# PMIC.net
KiCad netlist of a schematic drawn in Altium Designer
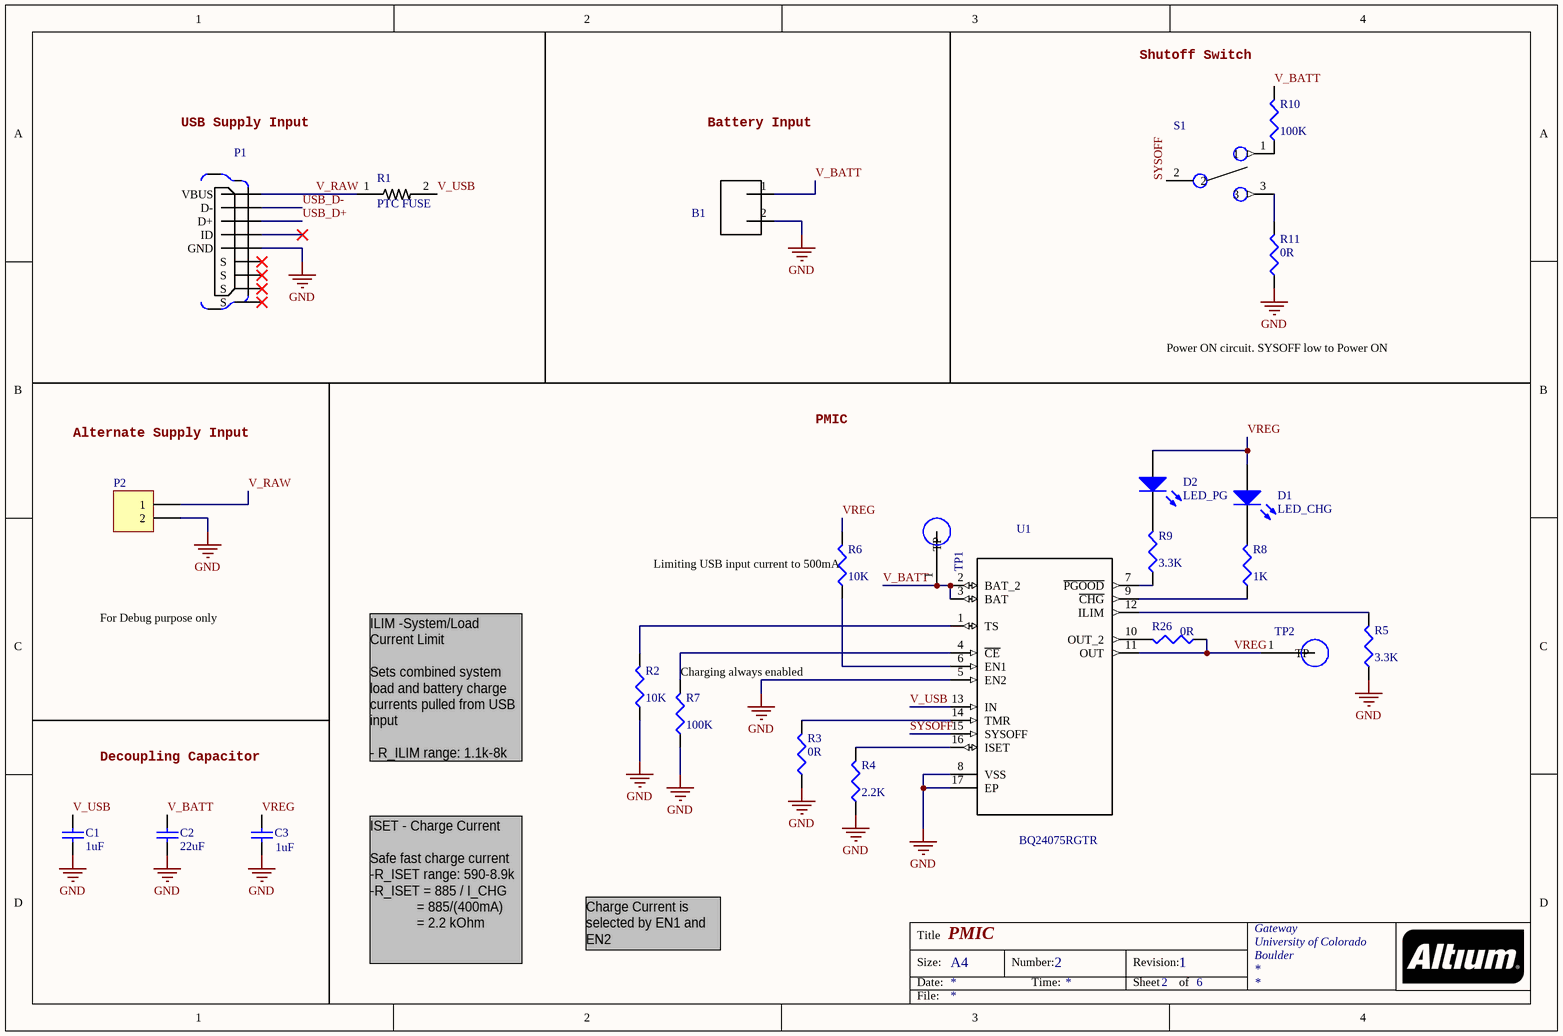
[diagram p0: PMIC.SchDoc]

(export (version "E")
  (design (tool "Eeschema 10.0.6"))
  (components
    (comp (ref "B1")
      (value "VBATT")
      (footprint "S2B-PH-SM4-TB(LF)(SN)")
      (description "CONN HEADER PH SIDE 2POS 2MM SMD")
      (fields
        (field (name "DIGI-KEY PART NUMBER") "455-1749-1-ND")
        (field (name "MANUFACTURER") "JST Sales America Inc.")
      )
      (libsource (lib "S2B-PH-SM4-TB_LF__SN_") (part "S2B-PH-SM4-TB(LF)(SN)"))
    )
    (comp (ref "C1")
      (value "1uF")
      (footprint "1608[0603]")
      (description "CAP CER 1UF 10V X7R 0603")
      (fields
        (field (name "DIGI-KEY PART NUMBER") "1276-1946-1-ND")
        (field (name "MANUFACTURER") "Samsung Electro-Mechanics")
      )
      (libsource (lib "Miscellaneous Devices") (part "Cap Semi"))
    )
    (comp (ref "C2")
      (value "22uF")
      (footprint "1608[0603]")
      (description "CAP CER 22UF 10V X5R 0603")
      (fields
        (field (name "MANUFACTURER") "Samsung Electro-Mechanics")
        (field (name "MANUFACTURER PART NUMBER") "CL10A226MPCNUBE")
        (field (name "PUBLISHER") "Altium Limited")
      )
      (libsource (lib "Miscellaneous Devices") (part "Cap"))
    )
    (comp (ref "C3")
      (value "1uF")
      (footprint "1608[0603]")
      (description "CAP CER 1UF 10V X7R 0603")
      (fields
        (field (name "DIGI-KEY PART NUMBER") "1276-1946-1-ND")
        (field (name "MANUFACTURER") "Samsung Electro-Mechanics")
      )
      (libsource (lib "Miscellaneous Devices") (part "Cap Semi"))
    )
    (comp (ref "D1")
      (value "LED_CHG")
      (footprint "1608[0603]")
      (description "Blue 470nm LED Indication - Discrete 2.85V 0603 (1608 Metric)")
      (fields
        (field (name "DIGI-KEY PART NUMBER") "475-2816-1-ND")
        (field (name "MANUFACTURER") "OSRAM Opto Semiconductors Inc.")
      )
      (libsource (lib "Miscellaneous Devices") (part "LED2"))
    )
    (comp (ref "D2")
      (value "LED_PG")
      (footprint "1608[0603]")
      (description "LED GREEN DIFFUSED 0603 SMD")
      (fields
        (field (name "DIGI-KEY PART NUMBER") "475-3118-1-ND")
        (field (name "MANUFACTURER") "OSRAM Opto Semiconductors Inc.")
      )
      (libsource (lib "Miscellaneous Devices") (part "LED2"))
    )
    (comp (ref "P1")
      (value "10104111-0001LF")
      (footprint "FRAMATOME_10104111-0001LF")
      (description "Micro Usb, 2.0 Type Ab, Receptacle, Th")
      (fields
        (field (name "DIGI-KEY PART NUMBER") "609-4053-1-ND")
        (field (name "MANUFACTURER") "Amphenol FCI")
      )
      (libsource (lib "USB-connector") (part "10104111-0001LF"))
    )
    (comp (ref "P2")
      (value "~")
      (footprint "HDR1X2")
      (description "Header, 2-Pin")
      (libsource (lib "Miscellaneous Connectors") (part "Header 2"))
    )
    (comp (ref "R1")
      (value "PTC FUSE")
      (footprint "RESC3216X125N")
      (description "PTC RESET FUSE 6V 500MA 1206")
      (fields (field (name "MANUFACTURER") "Bel Fuse") (field (name "MP") "0ZCA0075FF2G"))
      (libsource (lib "PTC-1206") (part "0ZCA0075FF2G"))
    )
    (comp (ref "R2")
      (value "10K")
      (footprint "1608[0603]")
      (description "RES SMD 10K OHM 1% 1/8W 0603")
      (fields
        (field (name "DIGI-KEY PART NUMBER") "MCT0603-10.0K-CFCT-ND")
        (field (name "MANUFACTURER") "Vishay Beyschlag")
      )
      (libsource (lib "Miscellaneous Devices") (part "Res3"))
    )
    (comp (ref "R3")
      (value "0R")
      (footprint "1608[0603]")
      (description "RES 0 OHM JUMPER 1/8W 0603")
      (fields
        (field (name "DIGI-KEY PART NUMBER") "749-1745-1-ND")
        (field (name "MANUFACTURER") "Vishay Beyschlag")
        (field (name "PUBLISHER") "Altium Limited")
      )
      (libsource (lib "Miscellaneous Devices") (part "Res3"))
    )
    (comp (ref "R4")
      (value "2.2K")
      (footprint "1608[0603]")
      (description "RES SMD 2.2K OHM 1% 1/10W 0603")
      (fields
        (field (name "DIGI-KEY PART NUMBER") "P2.20KHCT-ND")
        (field (name "MANUFACTURER") "Panasonic Electronic Components")
      )
      (libsource (lib "Miscellaneous Devices") (part "Res3"))
    )
    (comp (ref "R5")
      (value "3.3K")
      (footprint "1608[0603]")
      (description "RES SMD 3.3K OHM 5% 1/10W 0603")
      (fields
        (field (name "DIGI-KEY PART NUMBER") "P3.3KGCT-ND")
        (field (name "MANUFACTURER") "Panasonic Electronic Components")
      )
      (libsource (lib "Miscellaneous Devices") (part "Res3"))
    )
    (comp (ref "R6")
      (value "10K")
      (footprint "1608[0603]")
      (description "RES SMD 10K OHM 1% 1/8W 0603")
      (fields
        (field (name "DIGI-KEY PART NUMBER") "MCT0603-10.0K-CFCT-ND")
        (field (name "MANUFACTURER") "Vishay Beyschlag")
      )
      (libsource (lib "Miscellaneous Devices") (part "Res3"))
    )
    (comp (ref "R7")
      (value "100K")
      (footprint "1608[0603]")
      (description "RES SMD 100K OHM 0.1% 1/10W 0603")
      (fields (field (name "DIGI-KEY PART NUMBER") "RG16P100KBCT-ND") (field (name "MANUFACTURER") "Susumu"))
      (libsource (lib "Miscellaneous Devices") (part "Res3"))
    )
    (comp (ref "R8")
      (value "1K")
      (footprint "1608[0603]")
      (description "RES SMD 1K OHM 1% 1/8W 0603")
      (fields
        (field (name "DIGI-KEY PART NUMBER") "MCT0603-1.00K-CFCT-ND")
        (field (name "MANUFACTURER") "Vishay Beyschlag")
      )
      (libsource (lib "Miscellaneous Devices") (part "Res3"))
    )
    (comp (ref "R9")
      (value "3.3K")
      (footprint "1608[0603]")
      (description "RES SMD 3.3K OHM 5% 1/10W 0603")
      (fields
        (field (name "DIGI-KEY PART NUMBER") "P3.3KGCT-ND")
        (field (name "MANUFACTURER") "Panasonic Electronic Components")
      )
      (libsource (lib "Miscellaneous Devices") (part "Res3"))
    )
    (comp (ref "R10")
      (value "100K")
      (footprint "1608[0603]")
      (description "RES SMD 100K OHM 0.1% 1/10W 0603")
      (fields (field (name "DIGI-KEY PART NUMBER") "RG16P100KBCT-ND") (field (name "MANUFACTURER") "Susumu"))
      (libsource (lib "Miscellaneous Devices") (part "Res3"))
    )
    (comp (ref "R11")
      (value "0R")
      (footprint "1608[0603]")
      (description "RES 0 OHM JUMPER 1/8W 0603")
      (fields
        (field (name "DIGI-KEY PART NUMBER") "749-1745-1-ND")
        (field (name "MANUFACTURER") "Vishay Beyschlag")
        (field (name "PUBLISHER") "Altium Limited")
      )
      (libsource (lib "Miscellaneous Devices") (part "Res3"))
    )
    (comp (ref "R26")
      (value "0R")
      (footprint "1608[0603]")
      (description "RES 0 OHM JUMPER 1/8W 0603")
      (fields
        (field (name "DIGI-KEY PART NUMBER") "749-1745-1-ND")
        (field (name "MANUFACTURER") "Vishay Beyschlag")
        (field (name "PUBLISHER") "Altium Limited")
      )
      (libsource (lib "Miscellaneous Devices") (part "Res3"))
    )
    (comp (ref "S1")
      (value "AYZ0102AGRLC")
      (footprint "SW_AYZ0102AGRLC")
      (description "SWITCH SLIDE SPDT 100MA 12V")
      (fields (field (name "DIGI-KEY PART NUMBER") "401-2012-1-ND") (field (name "MANUFACTURER") "C&K"))
      (libsource (lib "AYZ0102AGRLC") (part "AYZ0102AGRLC"))
    )
    (comp (ref "TP1")
      (value "VBATT_TP")
      (footprint "TP380X203")
      (description "PC TEST POINT MINIATURE")
      (fields (field (name "MP") "5019") (field (name "DIGI-KEY_PART_NUMBER") "36-5019CT-ND"))
      (libsource (lib "5019") (part "5019"))
    )
    (comp (ref "TP2")
      (value "VREG_TP")
      (footprint "TP380X203")
      (description "PC TEST POINT MINIATURE")
      (fields (field (name "MP") "5019") (field (name "DIGI-KEY_PART_NUMBER") "36-5019CT-ND"))
      (libsource (lib "5019") (part "5019"))
    )
    (comp (ref "U1")
      (value "BQ24075RGTR")
      (footprint "QFN50P300X300X100-17N")
      (description "IC LI-ION CHARGE MGMT 16-QFN")
      (fields
        (field (name "MANUFACTURER PART NUMBER") "BQ24075RGTT")
        (field (name "MANUFACTURER") "Texas Instruments")
      )
      (libsource (lib "BQ24075RGTT") (part "BQ24075RGTT"))
    )
  )
  (nets
    (net (code "1") (name "/SYSOFF") (class "Default")
      (node (ref "S1") (pin "2") (pinfunction "2_2") (pintype "power_in"))
      (node (ref "U1") (pin "15") (pinfunction "SYSOFF_15") (pintype "input"))
    )
    (net (code "2") (name "/USB_D+") (class "Default")
      (node (ref "P1") (pin "3") (pinfunction "D+_3") (pintype "passive"))
    )
    (net (code "3") (name "/USB_D-") (class "Default")
      (node (ref "P1") (pin "2") (pinfunction "D-_2") (pintype "passive"))
    )
    (net (code "4") (name "/VREG") (class "Default")
      (node (ref "C3") (pin "2") (pinfunction "2_2") (pintype "passive"))
      (node (ref "D1") (pin "1") (pinfunction "A_1") (pintype "passive"))
      (node (ref "D2") (pin "1") (pinfunction "A_1") (pintype "passive"))
      (node (ref "R26") (pin "1") (pinfunction "1_1") (pintype "passive"))
      (node (ref "R6") (pin "2") (pinfunction "2_2") (pintype "passive"))
      (node (ref "TP2") (pin "1") (pinfunction "TP_1") (pintype "passive"))
      (node (ref "U1") (pin "11") (pinfunction "OUT_11") (pintype "output"))
    )
    (net (code "5") (name "/V_BATT") (class "Default")
      (node (ref "B1") (pin "1") (pinfunction "1_1") (pintype "passive"))
      (node (ref "C2") (pin "1") (pinfunction "1_1") (pintype "passive"))
      (node (ref "R10") (pin "2") (pinfunction "2_2") (pintype "passive"))
      (node (ref "TP1") (pin "1") (pinfunction "TP_1") (pintype "passive"))
      (node (ref "U1") (pin "2") (pinfunction "BAT_2_2") (pintype "bidirectional"))
      (node (ref "U1") (pin "3") (pinfunction "BAT_3") (pintype "bidirectional"))
    )
    (net (code "6") (name "/V_RAW") (class "Default")
      (node (ref "P1") (pin "1") (pinfunction "VBUS_1") (pintype "power_in"))
      (node (ref "P2") (pin "1") (pinfunction "1_1") (pintype "passive"))
      (node (ref "R1") (pin "1") (pinfunction "1_1") (pintype "passive"))
    )
    (net (code "7") (name "/V_USB") (class "Default")
      (node (ref "C1") (pin "2") (pinfunction "2_2") (pintype "passive"))
      (node (ref "R1") (pin "2") (pinfunction "2_2") (pintype "passive"))
      (node (ref "U1") (pin "13") (pinfunction "IN_13") (pintype "input"))
    )
    (net (code "8") (name "GND") (class "Default")
      (node (ref "B1") (pin "2") (pinfunction "2_2") (pintype "passive"))
      (node (ref "C1") (pin "1") (pinfunction "1_1") (pintype "passive"))
      (node (ref "C2") (pin "2") (pinfunction "2_2") (pintype "passive"))
      (node (ref "C3") (pin "1") (pinfunction "1_1") (pintype "passive"))
      (node (ref "P1") (pin "5") (pinfunction "GND_5") (pintype "power_in"))
      (node (ref "P2") (pin "2") (pinfunction "2_2") (pintype "passive"))
      (node (ref "R11") (pin "1") (pinfunction "1_1") (pintype "passive"))
      (node (ref "R2") (pin "1") (pinfunction "1_1") (pintype "passive"))
      (node (ref "R3") (pin "1") (pinfunction "1_1") (pintype "passive"))
      (node (ref "R4") (pin "1") (pinfunction "1_1") (pintype "passive"))
      (node (ref "R5") (pin "1") (pinfunction "1_1") (pintype "passive"))
      (node (ref "R7") (pin "1") (pinfunction "1_1") (pintype "passive"))
      (node (ref "U1") (pin "17") (pinfunction "EP_17") (pintype "passive"))
      (node (ref "U1") (pin "5") (pinfunction "EN2_5") (pintype "input"))
      (node (ref "U1") (pin "8") (pinfunction "VSS_8") (pintype "passive"))
    )
    (net (code "9") (name "Net-(D1-K)") (class "Default")
      (node (ref "D1") (pin "2") (pinfunction "K_2") (pintype "passive"))
      (node (ref "R8") (pin "2") (pinfunction "2_2") (pintype "passive"))
    )
    (net (code "10") (name "Net-(D2-K)") (class "Default")
      (node (ref "D2") (pin "2") (pinfunction "K_2") (pintype "passive"))
      (node (ref "R9") (pin "2") (pinfunction "2_2") (pintype "passive"))
    )
    (net (code "11") (name "Net-(R10-Pad1)") (class "Default")
      (node (ref "R10") (pin "1") (pinfunction "1_1") (pintype "passive"))
      (node (ref "S1") (pin "1") (pinfunction "1_1") (pintype "output"))
    )
    (net (code "12") (name "Net-(R11-Pad2)") (class "Default")
      (node (ref "R11") (pin "2") (pinfunction "2_2") (pintype "passive"))
      (node (ref "S1") (pin "3") (pinfunction "3_3") (pintype "output"))
    )
    (net (code "13") (name "Net-(U1-EN1)") (class "Default")
      (node (ref "R6") (pin "1") (pinfunction "1_1") (pintype "passive"))
      (node (ref "U1") (pin "6") (pinfunction "EN1_6") (pintype "input"))
    )
    (net (code "14") (name "Net-(U1-ILIM)") (class "Default")
      (node (ref "R5") (pin "2") (pinfunction "2_2") (pintype "passive"))
      (node (ref "U1") (pin "12") (pinfunction "ILIM_12") (pintype "output"))
    )
    (net (code "15") (name "Net-(U1-ISET)") (class "Default")
      (node (ref "R4") (pin "2") (pinfunction "2_2") (pintype "passive"))
      (node (ref "U1") (pin "16") (pinfunction "ISET_16") (pintype "bidirectional"))
    )
    (net (code "16") (name "Net-(U1-OUT_2)") (class "Default")
      (node (ref "R26") (pin "2") (pinfunction "2_2") (pintype "passive"))
      (node (ref "U1") (pin "10") (pinfunction "OUT_2_10") (pintype "output"))
    )
    (net (code "17") (name "Net-(U1-TMR)") (class "Default")
      (node (ref "R3") (pin "2") (pinfunction "2_2") (pintype "passive"))
      (node (ref "U1") (pin "14") (pinfunction "TMR_14") (pintype "input"))
    )
    (net (code "18") (name "Net-(U1-TS)") (class "Default")
      (node (ref "R2") (pin "2") (pinfunction "2_2") (pintype "passive"))
      (node (ref "U1") (pin "1") (pinfunction "TS_1") (pintype "bidirectional"))
    )
    (net (code "19") (name "Net-(U1-~{CE})") (class "Default")
      (node (ref "R7") (pin "2") (pinfunction "2_2") (pintype "passive"))
      (node (ref "U1") (pin "4") (pinfunction "~{CE}_4") (pintype "input"))
    )
    (net (code "20") (name "Net-(U1-~{CHG})") (class "Default")
      (node (ref "R8") (pin "1") (pinfunction "1_1") (pintype "passive"))
      (node (ref "U1") (pin "9") (pinfunction "~{CHG}_9") (pintype "output"))
    )
    (net (code "21") (name "Net-(U1-~{PGOOD})") (class "Default")
      (node (ref "R9") (pin "1") (pinfunction "1_1") (pintype "passive"))
      (node (ref "U1") (pin "7") (pinfunction "~{PGOOD}_7") (pintype "output"))
    )
    (net (code "22") (name "unconnected-(P1-ID-Pad4)") (class "Default")
      (node (ref "P1") (pin "4") (pinfunction "ID_4") (pintype "passive+no_connect"))
    )
    (net (code "23") (name "unconnected-(P1-S-Pad6)") (class "Default")
      (node (ref "P1") (pin "6") (pinfunction "S_6") (pintype "power_in+no_connect"))
    )
    (net (code "24") (name "unconnected-(P1-S-Pad7)") (class "Default")
      (node (ref "P1") (pin "7") (pinfunction "S_7") (pintype "power_in+no_connect"))
    )
    (net (code "25") (name "unconnected-(P1-S-Pad8)") (class "Default")
      (node (ref "P1") (pin "8") (pinfunction "S_8") (pintype "power_in+no_connect"))
    )
    (net (code "26") (name "unconnected-(P1-S-Pad9)") (class "Default")
      (node (ref "P1") (pin "9") (pinfunction "S_9") (pintype "power_in+no_connect"))
    )
  )
)
